# STM.net
KiCad netlist of a schematic drawn in Altium Designer
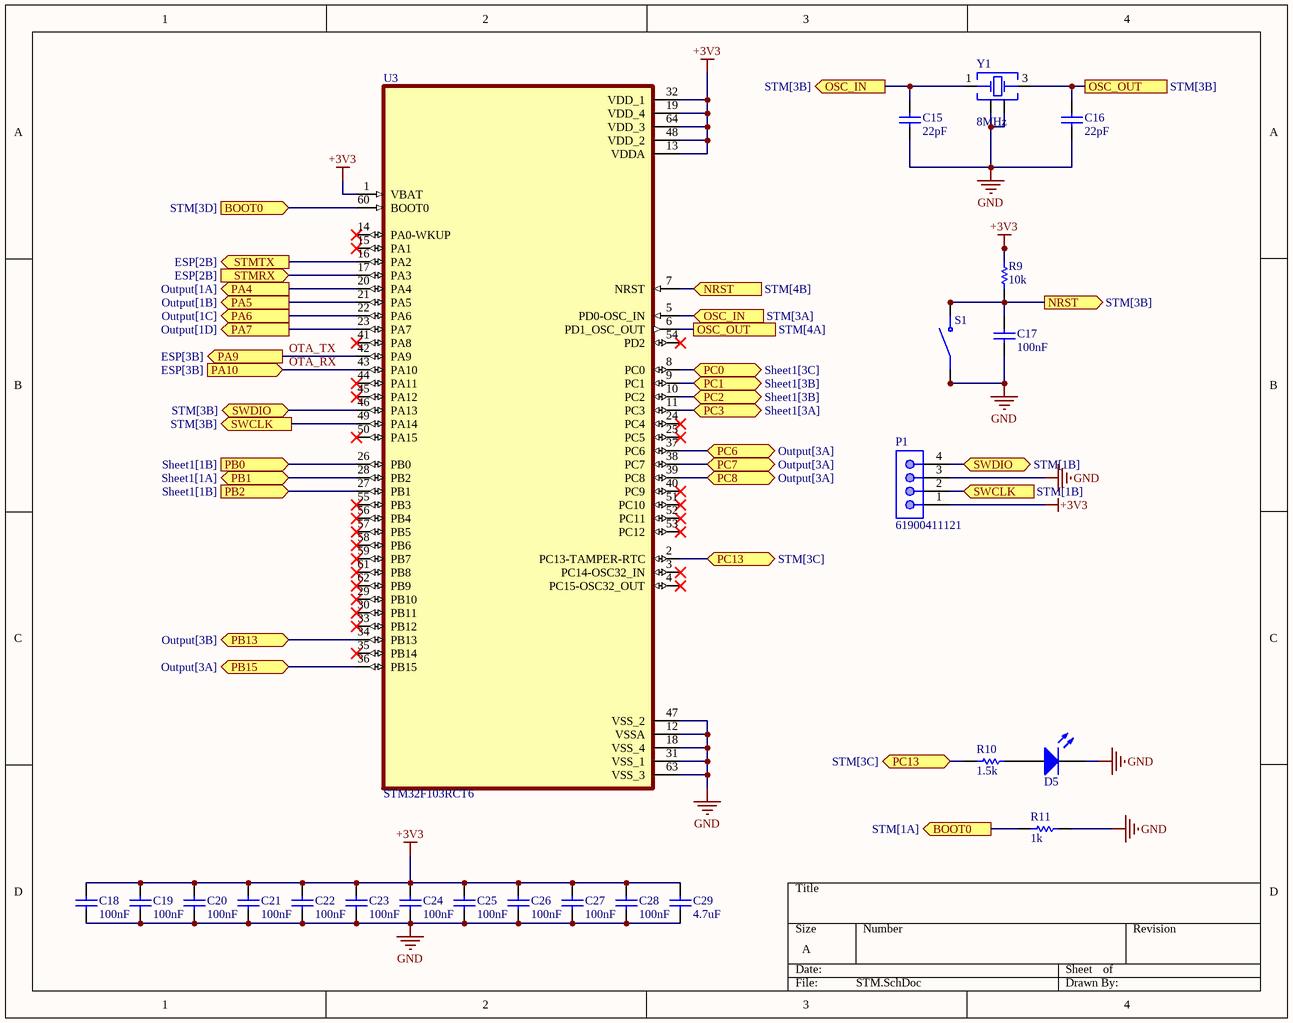
[diagram p0: STM.SchDoc]

(export (version "E")
  (design (tool "Eeschema 10.0.6"))
  (components
    (comp (ref "C15")
      (value "22pF")
      (footprint "CAP_0603")
      (description "CAP, size 0603, 22pF")
      (libsource (lib "SMIOT_Lib_Schematic") (part "01060322010"))
    )
    (comp (ref "C16")
      (value "22pF")
      (footprint "CAP_0603")
      (description "CAP, size 0603, 22pF")
      (libsource (lib "SMIOT_Lib_Schematic") (part "01060322010"))
    )
    (comp (ref "C17")
      (value "100nF")
      (footprint "CAP_0603")
      (description "CAP, size 0603, 100nF")
      (libsource (lib "SMIOT_Lib_Schematic") (part "01060310410"))
    )
    (comp (ref "C18")
      (value "100nF")
      (footprint "CAP_0603")
      (description "CAP, size 0603, 100nF")
      (libsource (lib "SMIOT_Lib_Schematic") (part "01060310410"))
    )
    (comp (ref "C19")
      (value "100nF")
      (footprint "CAP_0603")
      (description "CAP, size 0603, 100nF")
      (libsource (lib "SMIOT_Lib_Schematic") (part "01060310410"))
    )
    (comp (ref "C20")
      (value "100nF")
      (footprint "CAP_0603")
      (description "CAP, size 0603, 100nF")
      (libsource (lib "SMIOT_Lib_Schematic") (part "01060310410"))
    )
    (comp (ref "C21")
      (value "100nF")
      (footprint "CAP_0603")
      (description "CAP, size 0603, 100nF")
      (libsource (lib "SMIOT_Lib_Schematic") (part "01060310410"))
    )
    (comp (ref "C22")
      (value "100nF")
      (footprint "CAP_0603")
      (description "CAP, size 0603, 100nF")
      (libsource (lib "SMIOT_Lib_Schematic") (part "01060310410"))
    )
    (comp (ref "C23")
      (value "100nF")
      (footprint "CAP_0603")
      (description "CAP, size 0603, 100nF")
      (libsource (lib "SMIOT_Lib_Schematic") (part "01060310410"))
    )
    (comp (ref "C24")
      (value "100nF")
      (footprint "CAP_0603")
      (description "CAP, size 0603, 100nF")
      (libsource (lib "SMIOT_Lib_Schematic") (part "01060310410"))
    )
    (comp (ref "C25")
      (value "100nF")
      (footprint "CAP_0603")
      (description "CAP, size 0603, 100nF")
      (libsource (lib "SMIOT_Lib_Schematic") (part "01060310410"))
    )
    (comp (ref "C26")
      (value "100nF")
      (footprint "CAP_0603")
      (description "CAP, size 0603, 100nF")
      (libsource (lib "SMIOT_Lib_Schematic") (part "01060310410"))
    )
    (comp (ref "C27")
      (value "100nF")
      (footprint "CAP_0603")
      (description "CAP, size 0603, 100nF")
      (libsource (lib "SMIOT_Lib_Schematic") (part "01060310410"))
    )
    (comp (ref "C28")
      (value "100nF")
      (footprint "CAP_0603")
      (description "CAP, size 0603, 100nF")
      (libsource (lib "SMIOT_Lib_Schematic") (part "01060310410"))
    )
    (comp (ref "C29")
      (value "4.7uF")
      (footprint "CAP_0603")
      (description "CAP, size 0603, 1uF")
      (libsource (lib "SMIOT_Lib_Schematic") (part "01060310510"))
    )
    (comp (ref "D5")
      (value "LED SMD")
      (footprint "LED_0805_Blue")
      (description "LED")
      (libsource (lib "SMIOT_Lib_Schematic") (part "LED SMD"))
    )
    (comp (ref "P1")
      (value "61900411121")
      (footprint "61900411121")
      (description "WR-WTB THT Male Vertical Locking Header, pitch 2.54mm, 4p")
      (fields (field (name "PUBLISHER") "Wurth Elektronik"))
      (libsource (lib "Board_C24") (part "61900411121"))
    )
    (comp (ref "R9")
      (value "10k")
      (footprint "resistor_0603")
      (description "RES, 10k Ohm, size 0603, 1%")
      (libsource (lib "SMIOT_Lib_Schematic") (part "0006031031"))
    )
    (comp (ref "R10")
      (value "1.5k")
      (footprint "resistor_0603")
      (description "RES, 1.5 kOhms, size 0603, 1%")
      (libsource (lib "SMIOT_Lib_Schematic") (part "0006031521"))
    )
    (comp (ref "R11")
      (value "1k")
      (footprint "resistor_0603")
      (description "RES, 10k Ohm, size 0603, 1%")
      (libsource (lib "SMIOT_Lib_Schematic") (part "0006031031"))
    )
    (comp (ref "S1")
      (value "~")
      (footprint "SW_8-1437565-1")
      (fields (field (name "MP") "8-1437565-1"))
      (libsource (lib "8-1437565-1") (part "8-1437565-1"))
    )
    (comp (ref "U3")
      (value "STM32F103RCT6")
      (footprint "QFP50P1200X1200X160-64N")
      (description "ARMÂ® CortexÂ®-M3 STM32F1 Microcontroller IC 32-Bit 72MHz 256KB (256K x 8) FLASH 64-LQFP (10x10)")
      (fields (field (name "MF") "STMicroelectronics"))
      (libsource (lib "STM32F103RCT6") (part "STM32F103RCT6"))
    )
    (comp (ref "Y1")
      (value "8MHz")
      (footprint "WE-XTAL_CFPX-104")
      (description "WE-XTAL Quartz Crystal, SMT, CFPX-104, 8MHz, +/-20ppm")
      (fields
        (field (name "MANUFACTURER PART NUMBER") "830106162701")
        (field (name "MANUFACTURER") "Wurth Elektronik")
      )
      (libsource (lib "Board_C24") (part "830106162701"))
    )
  )
  (nets
    (net (code "1") (name "+3V3") (class "Default")
      (node (ref "C18") (pin "2") (pinfunction "2_2") (pintype "passive"))
      (node (ref "C19") (pin "2") (pinfunction "2_2") (pintype "passive"))
      (node (ref "C20") (pin "2") (pinfunction "2_2") (pintype "passive"))
      (node (ref "C21") (pin "2") (pinfunction "2_2") (pintype "passive"))
      (node (ref "C22") (pin "2") (pinfunction "2_2") (pintype "passive"))
      (node (ref "C23") (pin "1") (pinfunction "1_1") (pintype "passive"))
      (node (ref "C24") (pin "2") (pinfunction "2_2") (pintype "passive"))
      (node (ref "C25") (pin "2") (pinfunction "2_2") (pintype "passive"))
      (node (ref "C26") (pin "2") (pinfunction "2_2") (pintype "passive"))
      (node (ref "C27") (pin "2") (pinfunction "2_2") (pintype "passive"))
      (node (ref "C28") (pin "2") (pinfunction "2_2") (pintype "passive"))
      (node (ref "C29") (pin "2") (pinfunction "2_2") (pintype "passive"))
      (node (ref "P1") (pin "1") (pinfunction "1_1") (pintype "passive"))
      (node (ref "R9") (pin "2") (pinfunction "2_2") (pintype "passive"))
      (node (ref "U3") (pin "1") (pinfunction "VBAT_1") (pintype "input"))
      (node (ref "U3") (pin "13") (pinfunction "VDDA_13") (pintype "power_in"))
      (node (ref "U3") (pin "19") (pinfunction "VDD_4_19") (pintype "power_in"))
      (node (ref "U3") (pin "32") (pinfunction "VDD_1_32") (pintype "power_in"))
      (node (ref "U3") (pin "48") (pinfunction "VDD_2_48") (pintype "power_in"))
      (node (ref "U3") (pin "64") (pinfunction "VDD_3_64") (pintype "power_in"))
    )
    (net (code "2") (name "/BOOT0") (class "Default")
      (node (ref "R11") (pin "1") (pinfunction "1_1") (pintype "passive"))
      (node (ref "U3") (pin "60") (pinfunction "BOOT0_60") (pintype "input"))
    )
    (net (code "3") (name "/NRST") (class "Default")
      (node (ref "C17") (pin "2") (pinfunction "2_2") (pintype "passive"))
      (node (ref "R9") (pin "1") (pinfunction "1_1") (pintype "passive"))
      (node (ref "S1") (pin "3") (pinfunction "NO_3") (pintype "passive"))
      (node (ref "S1") (pin "4") (pinfunction "NO_4") (pintype "passive"))
      (node (ref "U3") (pin "7") (pinfunction "NRST_7") (pintype "input"))
    )
    (net (code "4") (name "/OSC_IN") (class "Default")
      (node (ref "C15") (pin "2") (pinfunction "2_2") (pintype "passive"))
      (node (ref "U3") (pin "5") (pinfunction "PD0-OSC_IN_5") (pintype "input"))
      (node (ref "Y1") (pin "1") (pinfunction "OSC1_1") (pintype "passive"))
    )
    (net (code "5") (name "/OSC_OUT") (class "Default")
      (node (ref "C16") (pin "2") (pinfunction "2_2") (pintype "passive"))
      (node (ref "U3") (pin "6") (pinfunction "PD1_OSC_OUT_6") (pintype "output"))
      (node (ref "Y1") (pin "3") (pinfunction "OSC2_3") (pintype "passive"))
    )
    (net (code "6") (name "/OTA_RX") (class "Default")
      (node (ref "U3") (pin "43") (pinfunction "PA10_43") (pintype "bidirectional"))
    )
    (net (code "7") (name "/OTA_TX") (class "Default")
      (node (ref "U3") (pin "42") (pinfunction "PA9_42") (pintype "bidirectional"))
    )
    (net (code "8") (name "/PA4") (class "Default")
      (node (ref "U3") (pin "20") (pinfunction "PA4_20") (pintype "bidirectional"))
    )
    (net (code "9") (name "/PA5") (class "Default")
      (node (ref "U3") (pin "21") (pinfunction "PA5_21") (pintype "bidirectional"))
    )
    (net (code "10") (name "/PA6") (class "Default")
      (node (ref "U3") (pin "22") (pinfunction "PA6_22") (pintype "bidirectional"))
    )
    (net (code "11") (name "/PA7") (class "Default")
      (node (ref "U3") (pin "23") (pinfunction "PA7_23") (pintype "bidirectional"))
    )
    (net (code "12") (name "/PB0") (class "Default")
      (node (ref "U3") (pin "26") (pinfunction "PB0_26") (pintype "bidirectional"))
    )
    (net (code "13") (name "/PB1") (class "Default")
      (node (ref "U3") (pin "28") (pinfunction "PB2_28") (pintype "bidirectional"))
    )
    (net (code "14") (name "/PB2") (class "Default")
      (node (ref "U3") (pin "27") (pinfunction "PB1_27") (pintype "bidirectional"))
    )
    (net (code "15") (name "/PB13") (class "Default")
      (node (ref "U3") (pin "34") (pinfunction "PB13_34") (pintype "bidirectional"))
    )
    (net (code "16") (name "/PB15") (class "Default")
      (node (ref "U3") (pin "36") (pinfunction "PB15_36") (pintype "bidirectional"))
    )
    (net (code "17") (name "/PC0") (class "Default")
      (node (ref "U3") (pin "8") (pinfunction "PC0_8") (pintype "bidirectional"))
    )
    (net (code "18") (name "/PC1") (class "Default")
      (node (ref "U3") (pin "9") (pinfunction "PC1_9") (pintype "bidirectional"))
    )
    (net (code "19") (name "/PC2") (class "Default")
      (node (ref "U3") (pin "10") (pinfunction "PC2_10") (pintype "bidirectional"))
    )
    (net (code "20") (name "/PC3") (class "Default")
      (node (ref "U3") (pin "11") (pinfunction "PC3_11") (pintype "bidirectional"))
    )
    (net (code "21") (name "/PC6") (class "Default")
      (node (ref "U3") (pin "37") (pinfunction "PC6_37") (pintype "bidirectional"))
    )
    (net (code "22") (name "/PC7") (class "Default")
      (node (ref "U3") (pin "38") (pinfunction "PC7_38") (pintype "bidirectional"))
    )
    (net (code "23") (name "/PC8") (class "Default")
      (node (ref "U3") (pin "39") (pinfunction "PC8_39") (pintype "bidirectional"))
    )
    (net (code "24") (name "/PC13") (class "Default")
      (node (ref "R10") (pin "2") (pinfunction "2_2") (pintype "passive"))
      (node (ref "U3") (pin "2") (pinfunction "PC13-TAMPER-RTC_2") (pintype "bidirectional"))
    )
    (net (code "25") (name "/STMRX") (class "Default")
      (node (ref "U3") (pin "17") (pinfunction "PA3_17") (pintype "bidirectional"))
    )
    (net (code "26") (name "/STMTX") (class "Default")
      (node (ref "U3") (pin "16") (pinfunction "PA2_16") (pintype "bidirectional"))
    )
    (net (code "27") (name "/SWCLK") (class "Default")
      (node (ref "P1") (pin "2") (pinfunction "2_2") (pintype "passive"))
      (node (ref "U3") (pin "49") (pinfunction "PA14_49") (pintype "bidirectional"))
    )
    (net (code "28") (name "/SWDIO") (class "Default")
      (node (ref "P1") (pin "4") (pinfunction "4_4") (pintype "passive"))
      (node (ref "U3") (pin "46") (pinfunction "PA13_46") (pintype "bidirectional"))
    )
    (net (code "29") (name "GND") (class "Default")
      (node (ref "C15") (pin "1") (pinfunction "1_1") (pintype "passive"))
      (node (ref "C16") (pin "1") (pinfunction "1_1") (pintype "passive"))
      (node (ref "C17") (pin "1") (pinfunction "1_1") (pintype "passive"))
      (node (ref "C18") (pin "1") (pinfunction "1_1") (pintype "passive"))
      (node (ref "C19") (pin "1") (pinfunction "1_1") (pintype "passive"))
      (node (ref "C20") (pin "1") (pinfunction "1_1") (pintype "passive"))
      (node (ref "C21") (pin "1") (pinfunction "1_1") (pintype "passive"))
      (node (ref "C22") (pin "1") (pinfunction "1_1") (pintype "passive"))
      (node (ref "C23") (pin "2") (pinfunction "2_2") (pintype "passive"))
      (node (ref "C24") (pin "1") (pinfunction "1_1") (pintype "passive"))
      (node (ref "C25") (pin "1") (pinfunction "1_1") (pintype "passive"))
      (node (ref "C26") (pin "1") (pinfunction "1_1") (pintype "passive"))
      (node (ref "C27") (pin "1") (pinfunction "1_1") (pintype "passive"))
      (node (ref "C28") (pin "1") (pinfunction "1_1") (pintype "passive"))
      (node (ref "C29") (pin "1") (pinfunction "1_1") (pintype "passive"))
      (node (ref "D5") (pin "2") (pinfunction "K_2") (pintype "passive"))
      (node (ref "P1") (pin "3") (pinfunction "3_3") (pintype "passive"))
      (node (ref "R11") (pin "2") (pinfunction "2_2") (pintype "passive"))
      (node (ref "S1") (pin "1") (pinfunction "COM_1") (pintype "passive"))
      (node (ref "S1") (pin "2") (pinfunction "COM_2") (pintype "passive"))
      (node (ref "U3") (pin "12") (pinfunction "VSSA_12") (pintype "power_in"))
      (node (ref "U3") (pin "18") (pinfunction "VSS_4_18") (pintype "power_in"))
      (node (ref "U3") (pin "31") (pinfunction "VSS_1_31") (pintype "power_in"))
      (node (ref "U3") (pin "47") (pinfunction "VSS_2_47") (pintype "power_in"))
      (node (ref "U3") (pin "63") (pinfunction "VSS_3_63") (pintype "power_in"))
      (node (ref "Y1") (pin "2") (pinfunction "GND_2") (pintype "passive"))
      (node (ref "Y1") (pin "4") (pinfunction "GND_4") (pintype "passive"))
    )
    (net (code "30") (name "Net-(D5-A)") (class "Default")
      (node (ref "D5") (pin "1") (pinfunction "A_1") (pintype "passive"))
      (node (ref "R10") (pin "1") (pinfunction "1_1") (pintype "passive"))
    )
    (net (code "31") (name "unconnected-(U3-PA0-WKUP-Pad14)") (class "Default")
      (node (ref "U3") (pin "14") (pinfunction "PA0-WKUP_14") (pintype "bidirectional+no_connect"))
    )
    (net (code "32") (name "unconnected-(U3-PA1-Pad15)") (class "Default")
      (node (ref "U3") (pin "15") (pinfunction "PA1_15") (pintype "bidirectional+no_connect"))
    )
    (net (code "33") (name "unconnected-(U3-PA8-Pad41)") (class "Default")
      (node (ref "U3") (pin "41") (pinfunction "PA8_41") (pintype "bidirectional+no_connect"))
    )
    (net (code "34") (name "unconnected-(U3-PA11-Pad44)") (class "Default")
      (node (ref "U3") (pin "44") (pinfunction "PA11_44") (pintype "bidirectional+no_connect"))
    )
    (net (code "35") (name "unconnected-(U3-PA12-Pad45)") (class "Default")
      (node (ref "U3") (pin "45") (pinfunction "PA12_45") (pintype "bidirectional+no_connect"))
    )
    (net (code "36") (name "unconnected-(U3-PA15-Pad50)") (class "Default")
      (node (ref "U3") (pin "50") (pinfunction "PA15_50") (pintype "bidirectional+no_connect"))
    )
    (net (code "37") (name "unconnected-(U3-PB3-Pad55)") (class "Default")
      (node (ref "U3") (pin "55") (pinfunction "PB3_55") (pintype "bidirectional+no_connect"))
    )
    (net (code "38") (name "unconnected-(U3-PB4-Pad56)") (class "Default")
      (node (ref "U3") (pin "56") (pinfunction "PB4_56") (pintype "bidirectional+no_connect"))
    )
    (net (code "39") (name "unconnected-(U3-PB5-Pad57)") (class "Default")
      (node (ref "U3") (pin "57") (pinfunction "PB5_57") (pintype "bidirectional+no_connect"))
    )
    (net (code "40") (name "unconnected-(U3-PB6-Pad58)") (class "Default")
      (node (ref "U3") (pin "58") (pinfunction "PB6_58") (pintype "bidirectional+no_connect"))
    )
    (net (code "41") (name "unconnected-(U3-PB7-Pad59)") (class "Default")
      (node (ref "U3") (pin "59") (pinfunction "PB7_59") (pintype "bidirectional+no_connect"))
    )
    (net (code "42") (name "unconnected-(U3-PB8-Pad61)") (class "Default")
      (node (ref "U3") (pin "61") (pinfunction "PB8_61") (pintype "bidirectional+no_connect"))
    )
    (net (code "43") (name "unconnected-(U3-PB9-Pad62)") (class "Default")
      (node (ref "U3") (pin "62") (pinfunction "PB9_62") (pintype "bidirectional+no_connect"))
    )
    (net (code "44") (name "unconnected-(U3-PB10-Pad29)") (class "Default")
      (node (ref "U3") (pin "29") (pinfunction "PB10_29") (pintype "bidirectional+no_connect"))
    )
    (net (code "45") (name "unconnected-(U3-PB11-Pad30)") (class "Default")
      (node (ref "U3") (pin "30") (pinfunction "PB11_30") (pintype "bidirectional+no_connect"))
    )
    (net (code "46") (name "unconnected-(U3-PB12-Pad33)") (class "Default")
      (node (ref "U3") (pin "33") (pinfunction "PB12_33") (pintype "bidirectional+no_connect"))
    )
    (net (code "47") (name "unconnected-(U3-PB14-Pad35)") (class "Default")
      (node (ref "U3") (pin "35") (pinfunction "PB14_35") (pintype "bidirectional+no_connect"))
    )
    (net (code "48") (name "unconnected-(U3-PC4-Pad24)") (class "Default")
      (node (ref "U3") (pin "24") (pinfunction "PC4_24") (pintype "bidirectional+no_connect"))
    )
    (net (code "49") (name "unconnected-(U3-PC5-Pad25)") (class "Default")
      (node (ref "U3") (pin "25") (pinfunction "PC5_25") (pintype "bidirectional+no_connect"))
    )
    (net (code "50") (name "unconnected-(U3-PC9-Pad40)") (class "Default")
      (node (ref "U3") (pin "40") (pinfunction "PC9_40") (pintype "bidirectional+no_connect"))
    )
    (net (code "51") (name "unconnected-(U3-PC10-Pad51)") (class "Default")
      (node (ref "U3") (pin "51") (pinfunction "PC10_51") (pintype "bidirectional+no_connect"))
    )
    (net (code "52") (name "unconnected-(U3-PC11-Pad52)") (class "Default")
      (node (ref "U3") (pin "52") (pinfunction "PC11_52") (pintype "bidirectional+no_connect"))
    )
    (net (code "53") (name "unconnected-(U3-PC12-Pad53)") (class "Default")
      (node (ref "U3") (pin "53") (pinfunction "PC12_53") (pintype "bidirectional+no_connect"))
    )
    (net (code "54") (name "unconnected-(U3-PC14-OSC32_IN-Pad3)") (class "Default")
      (node (ref "U3") (pin "3") (pinfunction "PC14-OSC32_IN_3") (pintype "bidirectional+no_connect"))
    )
    (net (code "55") (name "unconnected-(U3-PC15-OSC32_OUT-Pad4)") (class "Default")
      (node (ref "U3") (pin "4") (pinfunction "PC15-OSC32_OUT_4") (pintype "bidirectional+no_connect"))
    )
    (net (code "56") (name "unconnected-(U3-PD2-Pad54)") (class "Default")
      (node (ref "U3") (pin "54") (pinfunction "PD2_54") (pintype "bidirectional+no_connect"))
    )
  )
)
